# memory_module.net
KiCad netlist of a schematic drawn in Altium Designer
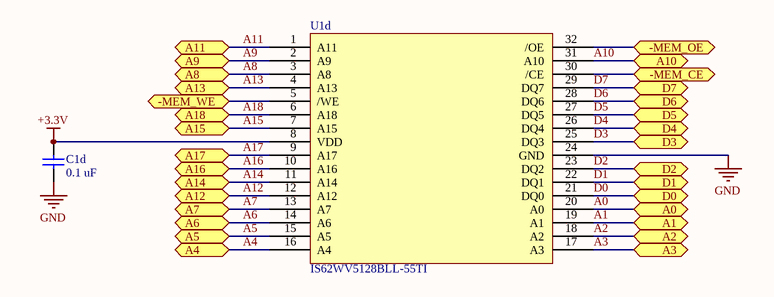
[diagram p0: memory module.SchDoc]

(export (version "E")
  (design (tool "Eeschema 10.0.6"))
  (components
    (comp (ref "C1d") (value "0.1 uF") (footprint "0603") (libsource (lib "allspace_schem") (part "Cap")))
    (comp (ref "U1d")
      (value "IS62WV5128BLL-55TI")
      (footprint "TSOP-32")
      (libsource (lib "allspace_schem") (part "IS62WV5128BLL-55TI"))
    )
  )
  (nets
    (net (code "1") (name "+3.3V") (class "Default")
      (node (ref "C1d") (pin "2") (pinfunction "2_2") (pintype "passive"))
      (node (ref "U1d") (pin "8") (pinfunction "VDD_8") (pintype "passive"))
    )
    (net (code "2") (name "/-MEM_CE") (class "Default")
      (node (ref "U1d") (pin "30") (pinfunction "/CE_30") (pintype "passive"))
    )
    (net (code "3") (name "/-MEM_OE") (class "Default")
      (node (ref "U1d") (pin "32") (pinfunction "/OE_32") (pintype "passive"))
    )
    (net (code "4") (name "/-MEM_WE") (class "Default")
      (node (ref "U1d") (pin "5") (pinfunction "/WE_5") (pintype "passive"))
    )
    (net (code "5") (name "/A0") (class "Default")
      (node (ref "U1d") (pin "20") (pinfunction "A0_20") (pintype "passive"))
    )
    (net (code "6") (name "/A1") (class "Default")
      (node (ref "U1d") (pin "19") (pinfunction "A1_19") (pintype "passive"))
    )
    (net (code "7") (name "/A2") (class "Default")
      (node (ref "U1d") (pin "18") (pinfunction "A2_18") (pintype "passive"))
    )
    (net (code "8") (name "/A3") (class "Default")
      (node (ref "U1d") (pin "17") (pinfunction "A3_17") (pintype "passive"))
    )
    (net (code "9") (name "/A4") (class "Default")
      (node (ref "U1d") (pin "16") (pinfunction "A4_16") (pintype "passive"))
    )
    (net (code "10") (name "/A5") (class "Default")
      (node (ref "U1d") (pin "15") (pinfunction "A5_15") (pintype "passive"))
    )
    (net (code "11") (name "/A6") (class "Default")
      (node (ref "U1d") (pin "14") (pinfunction "A6_14") (pintype "passive"))
    )
    (net (code "12") (name "/A7") (class "Default")
      (node (ref "U1d") (pin "13") (pinfunction "A7_13") (pintype "passive"))
    )
    (net (code "13") (name "/A8") (class "Default")
      (node (ref "U1d") (pin "3") (pinfunction "A8_3") (pintype "passive"))
    )
    (net (code "14") (name "/A9") (class "Default")
      (node (ref "U1d") (pin "2") (pinfunction "A9_2") (pintype "passive"))
    )
    (net (code "15") (name "/A10") (class "Default")
      (node (ref "U1d") (pin "31") (pinfunction "A10_31") (pintype "passive"))
    )
    (net (code "16") (name "/A11") (class "Default")
      (node (ref "U1d") (pin "1") (pinfunction "A11_1") (pintype "passive"))
    )
    (net (code "17") (name "/A12") (class "Default")
      (node (ref "U1d") (pin "12") (pinfunction "A12_12") (pintype "passive"))
    )
    (net (code "18") (name "/A13") (class "Default")
      (node (ref "U1d") (pin "4") (pinfunction "A13_4") (pintype "passive"))
    )
    (net (code "19") (name "/A14") (class "Default")
      (node (ref "U1d") (pin "11") (pinfunction "A14_11") (pintype "passive"))
    )
    (net (code "20") (name "/A15") (class "Default")
      (node (ref "U1d") (pin "7") (pinfunction "A15_7") (pintype "passive"))
    )
    (net (code "21") (name "/A16") (class "Default")
      (node (ref "U1d") (pin "10") (pinfunction "A16_10") (pintype "passive"))
    )
    (net (code "22") (name "/A17") (class "Default")
      (node (ref "U1d") (pin "9") (pinfunction "A17_9") (pintype "passive"))
    )
    (net (code "23") (name "/A18") (class "Default")
      (node (ref "U1d") (pin "6") (pinfunction "A18_6") (pintype "passive"))
    )
    (net (code "24") (name "/D0") (class "Default")
      (node (ref "U1d") (pin "21") (pinfunction "DQ0_21") (pintype "passive"))
    )
    (net (code "25") (name "/D1") (class "Default")
      (node (ref "U1d") (pin "22") (pinfunction "DQ1_22") (pintype "passive"))
    )
    (net (code "26") (name "/D2") (class "Default")
      (node (ref "U1d") (pin "23") (pinfunction "DQ2_23") (pintype "passive"))
    )
    (net (code "27") (name "/D3") (class "Default")
      (node (ref "U1d") (pin "25") (pinfunction "DQ3_25") (pintype "passive"))
    )
    (net (code "28") (name "/D4") (class "Default")
      (node (ref "U1d") (pin "26") (pinfunction "DQ4_26") (pintype "passive"))
    )
    (net (code "29") (name "/D5") (class "Default")
      (node (ref "U1d") (pin "27") (pinfunction "DQ5_27") (pintype "passive"))
    )
    (net (code "30") (name "/D6") (class "Default")
      (node (ref "U1d") (pin "28") (pinfunction "DQ6_28") (pintype "passive"))
    )
    (net (code "31") (name "/D7") (class "Default")
      (node (ref "U1d") (pin "29") (pinfunction "DQ7_29") (pintype "passive"))
    )
    (net (code "32") (name "GND") (class "Default")
      (node (ref "C1d") (pin "1") (pinfunction "1_1") (pintype "passive"))
      (node (ref "U1d") (pin "24") (pinfunction "GND_24") (pintype "passive"))
    )
  )
)
